# TutorialLED.net
KiCad netlist of a schematic drawn in Altium Designer
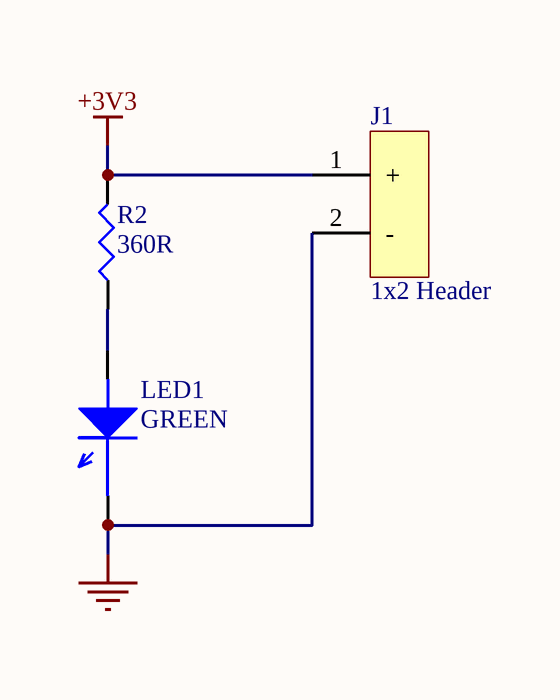
[diagram p0: TutorialLED.SchDoc]

(export (version "E")
  (design (tool "Eeschema 10.0.6"))
  (components
    (comp (ref "J1")
      (value "1x2 Header")
      (footprint "HDR1X2")
      (description "Board Connector, 2 Contact(s), 1 Row(s), Male, Straight, Solder Terminal")
      (fields (field (name "MANUFACTURER") "Molex") (field (name "MANUFACTURER PART NUMBER") "0022292021"))
      (libsource (lib "Clocked LED_Schlib") (part "0022292021"))
    )
    (comp (ref "LED1")
      (value "GREEN")
      (footprint "LED1206")
      (description "Single Color LED")
      (fields
        (field (name "MANUFACTURER") "Wurth Electronics")
        (field (name "MANUFACTURER PART NUMBER") "156120VS82500")
      )
      (libsource (lib "Clocked LED_Schlib") (part "156120VS82500"))
    )
    (comp (ref "R2")
      (value "360R")
      (footprint "Resistor")
      (fields
        (field (name "MANUFACTURER") "Vishay")
        (field (name "MANUFACTURER PART NUMBER") "CRCW0805360RFKEA")
        (field (name "TOLERANCE") "1%")
      )
      (libsource (lib "Clocked LED_Schlib") (part "CRCW0805360RFKEA"))
    )
  )
  (nets
    (net (code "1") (name "+3V3") (class "Default")
      (node (ref "J1") (pin "1") (pinfunction "+_1") (pintype "passive"))
      (node (ref "R2") (pin "2") (pinfunction "2_2") (pintype "passive"))
    )
    (net (code "2") (name "GND") (class "Default")
      (node (ref "J1") (pin "2") (pinfunction "-_2") (pintype "passive"))
      (node (ref "LED1") (pin "1") (pinfunction "1_1") (pintype "passive"))
    )
    (net (code "3") (name "Net-(LED1-Pad2)") (class "Default")
      (node (ref "LED1") (pin "2") (pinfunction "2_2") (pintype "passive"))
      (node (ref "R2") (pin "1") (pinfunction "1_1") (pintype "passive"))
    )
  )
)
